# pwmControl.net
KiCad netlist of a schematic drawn in EAGLE
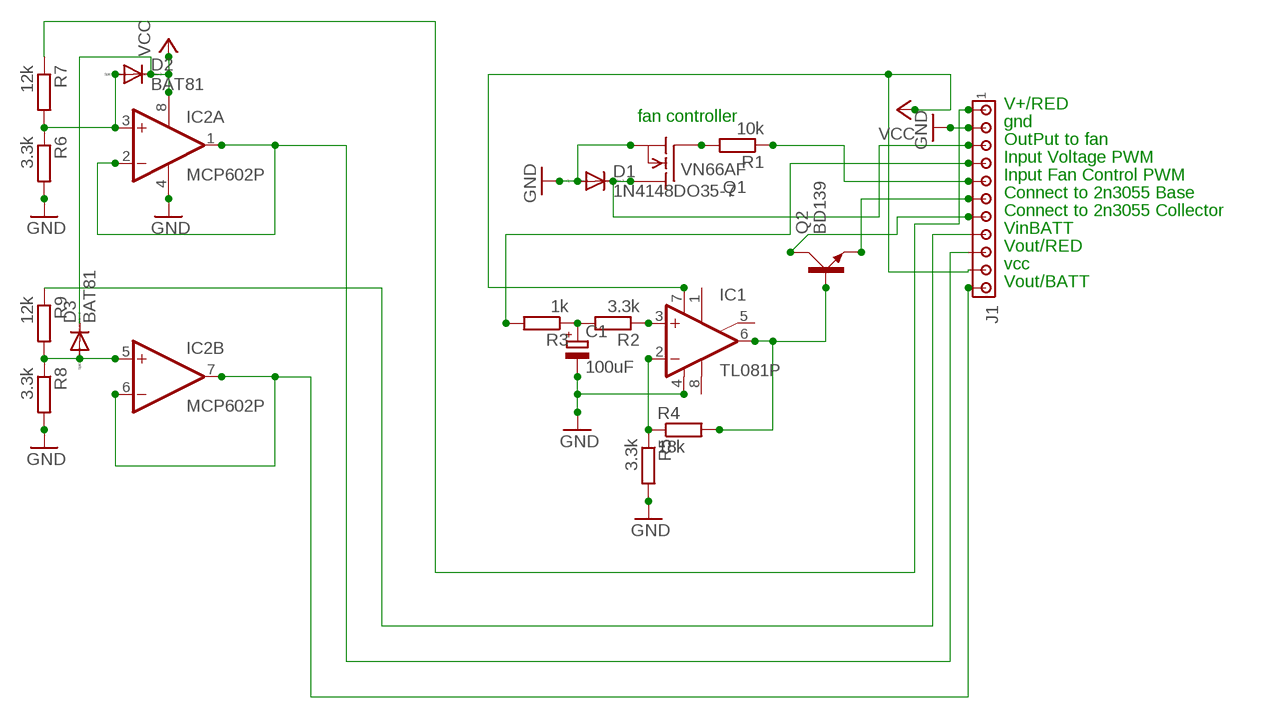
[diagram p0: schematic, sheet 1]

(export (version "E")
  (design (tool "Eeschema 10.0.6"))
  (components
    (comp (ref "C1")
      (value "100uF")
      (footprint "eagle-import:EB20D")
      (libsource (lib "eagle-import") (part "CPOL-EUE10-20"))
    )
    (comp (ref "D1")
      (value "1N4148DO35-7")
      (footprint "eagle-import:DO35-7")
      (libsource (lib "eagle-import") (part "1N4148DO35-7"))
    )
    (comp (ref "D2")
      (value "BAT81")
      (footprint "eagle-import:DO34-7")
      (libsource (lib "eagle-import") (part "BAT81"))
    )
    (comp (ref "D3")
      (value "BAT81")
      (footprint "eagle-import:DO34-7")
      (libsource (lib "eagle-import") (part "BAT81"))
    )
    (comp (ref "IC1")
      (value "TL081P")
      (footprint "eagle-import:DIL08")
      (libsource (lib "eagle-import") (part "TL081P"))
    )
    (comp (ref "IC2")
      (value "MCP602P")
      (footprint "eagle-import:DIL08")
      (libsource (lib "eagle-import") (part "MCP602P"))
    )
    (comp (ref "J1")
      (value "MTA11-156")
      (footprint "eagle-import:1X11MTA")
      (libsource (lib "eagle-import") (part "MTA11-156"))
    )
    (comp (ref "Q1")
      (value "VN66AF")
      (footprint "eagle-import:TO202")
      (libsource (lib "eagle-import") (part "VN66AF"))
    )
    (comp (ref "Q2")
      (value "BD139")
      (footprint "eagle-import:TO126AV")
      (libsource (lib "eagle-import") (part "BD139"))
    )
    (comp (ref "R1")
      (value "10k")
      (footprint "eagle-import:0207_10")
      (libsource (lib "eagle-import") (part "R-EU_0207/10"))
    )
    (comp (ref "R2")
      (value "3.3k")
      (footprint "eagle-import:0207_10")
      (libsource (lib "eagle-import") (part "R-EU_0207/10"))
    )
    (comp (ref "R3")
      (value "1k")
      (footprint "eagle-import:0207_10")
      (libsource (lib "eagle-import") (part "R-EU_0207/10"))
    )
    (comp (ref "R4")
      (value "18k")
      (footprint "eagle-import:0207_10")
      (libsource (lib "eagle-import") (part "R-EU_0207/10"))
    )
    (comp (ref "R5")
      (value "3.3k")
      (footprint "eagle-import:0207_10")
      (libsource (lib "eagle-import") (part "R-EU_0207/10"))
    )
    (comp (ref "R6")
      (value "3.3k")
      (footprint "eagle-import:0207_10")
      (libsource (lib "eagle-import") (part "R-EU_0207/10"))
    )
    (comp (ref "R7")
      (value "12k")
      (footprint "eagle-import:0207_10")
      (libsource (lib "eagle-import") (part "R-EU_0207/10"))
    )
    (comp (ref "R8")
      (value "3.3k")
      (footprint "eagle-import:0207_10")
      (libsource (lib "eagle-import") (part "R-EU_0207/10"))
    )
    (comp (ref "R9")
      (value "12k")
      (footprint "eagle-import:0207_10")
      (libsource (lib "eagle-import") (part "R-EU_0207/10"))
    )
  )
  (nets
    (net (code "1") (name "GND") (class "Default")
      (node (ref "C1") (pin "-") (pinfunction "-_-") (pintype "passive"))
      (node (ref "D1") (pin "A") (pinfunction "A_A") (pintype "passive"))
      (node (ref "IC1") (pin "4") (pinfunction "V-_4") (pintype "power_in"))
      (node (ref "IC2") (pin "4") (pinfunction "V-_4") (pintype "power_in"))
      (node (ref "J1") (pin "2") (pinfunction "2_2") (pintype "passive"))
      (node (ref "Q1") (pin "1") (pinfunction "S_1") (pintype "passive"))
      (node (ref "R5") (pin "2") (pinfunction "2_2") (pintype "passive"))
      (node (ref "R6") (pin "2") (pinfunction "2_2") (pintype "passive"))
      (node (ref "R8") (pin "2") (pinfunction "2_2") (pintype "passive"))
    )
    (net (code "2") (name "Net-(C1-Pad+)") (class "Default")
      (node (ref "C1") (pin "+") (pinfunction "+_+") (pintype "passive"))
      (node (ref "R2") (pin "2") (pinfunction "2_2") (pintype "passive"))
      (node (ref "R3") (pin "1") (pinfunction "1_1") (pintype "passive"))
    )
    (net (code "3") (name "Net-(IC1-+IN)") (class "Default")
      (node (ref "IC1") (pin "3") (pinfunction "+IN_3") (pintype "input"))
      (node (ref "R2") (pin "1") (pinfunction "1_1") (pintype "passive"))
    )
    (net (code "4") (name "Net-(IC1--IN)") (class "Default")
      (node (ref "IC1") (pin "2") (pinfunction "-IN_2") (pintype "input"))
      (node (ref "R4") (pin "1") (pinfunction "1_1") (pintype "passive"))
      (node (ref "R5") (pin "1") (pinfunction "1_1") (pintype "passive"))
    )
    (net (code "5") (name "Net-(IC1-OUT)") (class "Default")
      (node (ref "IC1") (pin "6") (pinfunction "OUT_6") (pintype "output"))
      (node (ref "Q2") (pin "B") (pinfunction "B_B") (pintype "passive"))
      (node (ref "R4") (pin "2") (pinfunction "2_2") (pintype "passive"))
    )
    (net (code "6") (name "Net-(IC2A-+IN)") (class "Default")
      (node (ref "D2") (pin "A") (pinfunction "A_A") (pintype "passive"))
      (node (ref "IC2") (pin "3") (pinfunction "+IN_3") (pintype "input"))
      (node (ref "R6") (pin "1") (pinfunction "1_1") (pintype "passive"))
      (node (ref "R7") (pin "2") (pinfunction "2_2") (pintype "passive"))
    )
    (net (code "7") (name "Net-(IC2A--IN)") (class "Default")
      (node (ref "IC2") (pin "1") (pinfunction "OUT_1") (pintype "output"))
      (node (ref "IC2") (pin "2") (pinfunction "-IN_2") (pintype "input"))
      (node (ref "J1") (pin "9") (pinfunction "9_9") (pintype "passive"))
    )
    (net (code "8") (name "Net-(IC2B-+IN)") (class "Default")
      (node (ref "D3") (pin "A") (pinfunction "A_A") (pintype "passive"))
      (node (ref "IC2") (pin "5") (pinfunction "+IN_5") (pintype "input"))
      (node (ref "R8") (pin "1") (pinfunction "1_1") (pintype "passive"))
      (node (ref "R9") (pin "2") (pinfunction "2_2") (pintype "passive"))
    )
    (net (code "9") (name "Net-(IC2B--IN)") (class "Default")
      (node (ref "IC2") (pin "6") (pinfunction "-IN_6") (pintype "input"))
      (node (ref "IC2") (pin "7") (pinfunction "OUT_7") (pintype "output"))
      (node (ref "J1") (pin "11") (pinfunction "11_11") (pintype "passive"))
    )
    (net (code "10") (name "Net-(J1-Pad1)") (class "Default")
      (node (ref "J1") (pin "1") (pinfunction "1_1") (pintype "passive"))
      (node (ref "R7") (pin "1") (pinfunction "1_1") (pintype "passive"))
    )
    (net (code "11") (name "Net-(J1-Pad4)") (class "Default")
      (node (ref "J1") (pin "4") (pinfunction "4_4") (pintype "passive"))
      (node (ref "R3") (pin "2") (pinfunction "2_2") (pintype "passive"))
    )
    (net (code "12") (name "Net-(J1-Pad5)") (class "Default")
      (node (ref "J1") (pin "5") (pinfunction "5_5") (pintype "passive"))
      (node (ref "R1") (pin "1") (pinfunction "1_1") (pintype "passive"))
    )
    (net (code "13") (name "Net-(J1-Pad6)") (class "Default")
      (node (ref "J1") (pin "6") (pinfunction "6_6") (pintype "passive"))
      (node (ref "Q2") (pin "E") (pinfunction "E_E") (pintype "passive"))
    )
    (net (code "14") (name "Net-(J1-Pad7)") (class "Default")
      (node (ref "J1") (pin "7") (pinfunction "7_7") (pintype "passive"))
      (node (ref "Q2") (pin "C") (pinfunction "C_C") (pintype "passive"))
    )
    (net (code "15") (name "Net-(J1-Pad8)") (class "Default")
      (node (ref "J1") (pin "8") (pinfunction "8_8") (pintype "passive"))
      (node (ref "R9") (pin "1") (pinfunction "1_1") (pintype "passive"))
    )
    (net (code "16") (name "Net-(Q1-D)") (class "Default")
      (node (ref "D1") (pin "C") (pinfunction "C_C") (pintype "passive"))
      (node (ref "J1") (pin "3") (pinfunction "3_3") (pintype "passive"))
      (node (ref "Q1") (pin "3") (pinfunction "D_3") (pintype "passive"))
    )
    (net (code "17") (name "Net-(Q1-G)") (class "Default")
      (node (ref "Q1") (pin "2") (pinfunction "G_2") (pintype "passive"))
      (node (ref "R1") (pin "2") (pinfunction "2_2") (pintype "passive"))
    )
    (net (code "18") (name "VCC") (class "Default")
      (node (ref "D2") (pin "C") (pinfunction "C_C") (pintype "passive"))
      (node (ref "D3") (pin "C") (pinfunction "C_C") (pintype "passive"))
      (node (ref "IC1") (pin "7") (pinfunction "V+_7") (pintype "power_in"))
      (node (ref "IC2") (pin "8") (pinfunction "V+_8") (pintype "power_in"))
      (node (ref "J1") (pin "10") (pinfunction "10_10") (pintype "passive"))
    )
    (net (code "19") (name "unconnected-(IC1-ON1-Pad1)") (class "Default")
      (node (ref "IC1") (pin "1") (pinfunction "ON1_1") (pintype "passive"))
    )
    (net (code "20") (name "unconnected-(IC1-ON2-Pad5)") (class "Default")
      (node (ref "IC1") (pin "5") (pinfunction "ON2_5") (pintype "passive"))
    )
    (net (code "21") (name "unconnected-(IC1-OPT-Pad8)") (class "Default")
      (node (ref "IC1") (pin "8") (pinfunction "OPT_8") (pintype "passive"))
    )
  )
)
